# MCU.net
KiCad netlist of a schematic drawn in Altium Designer
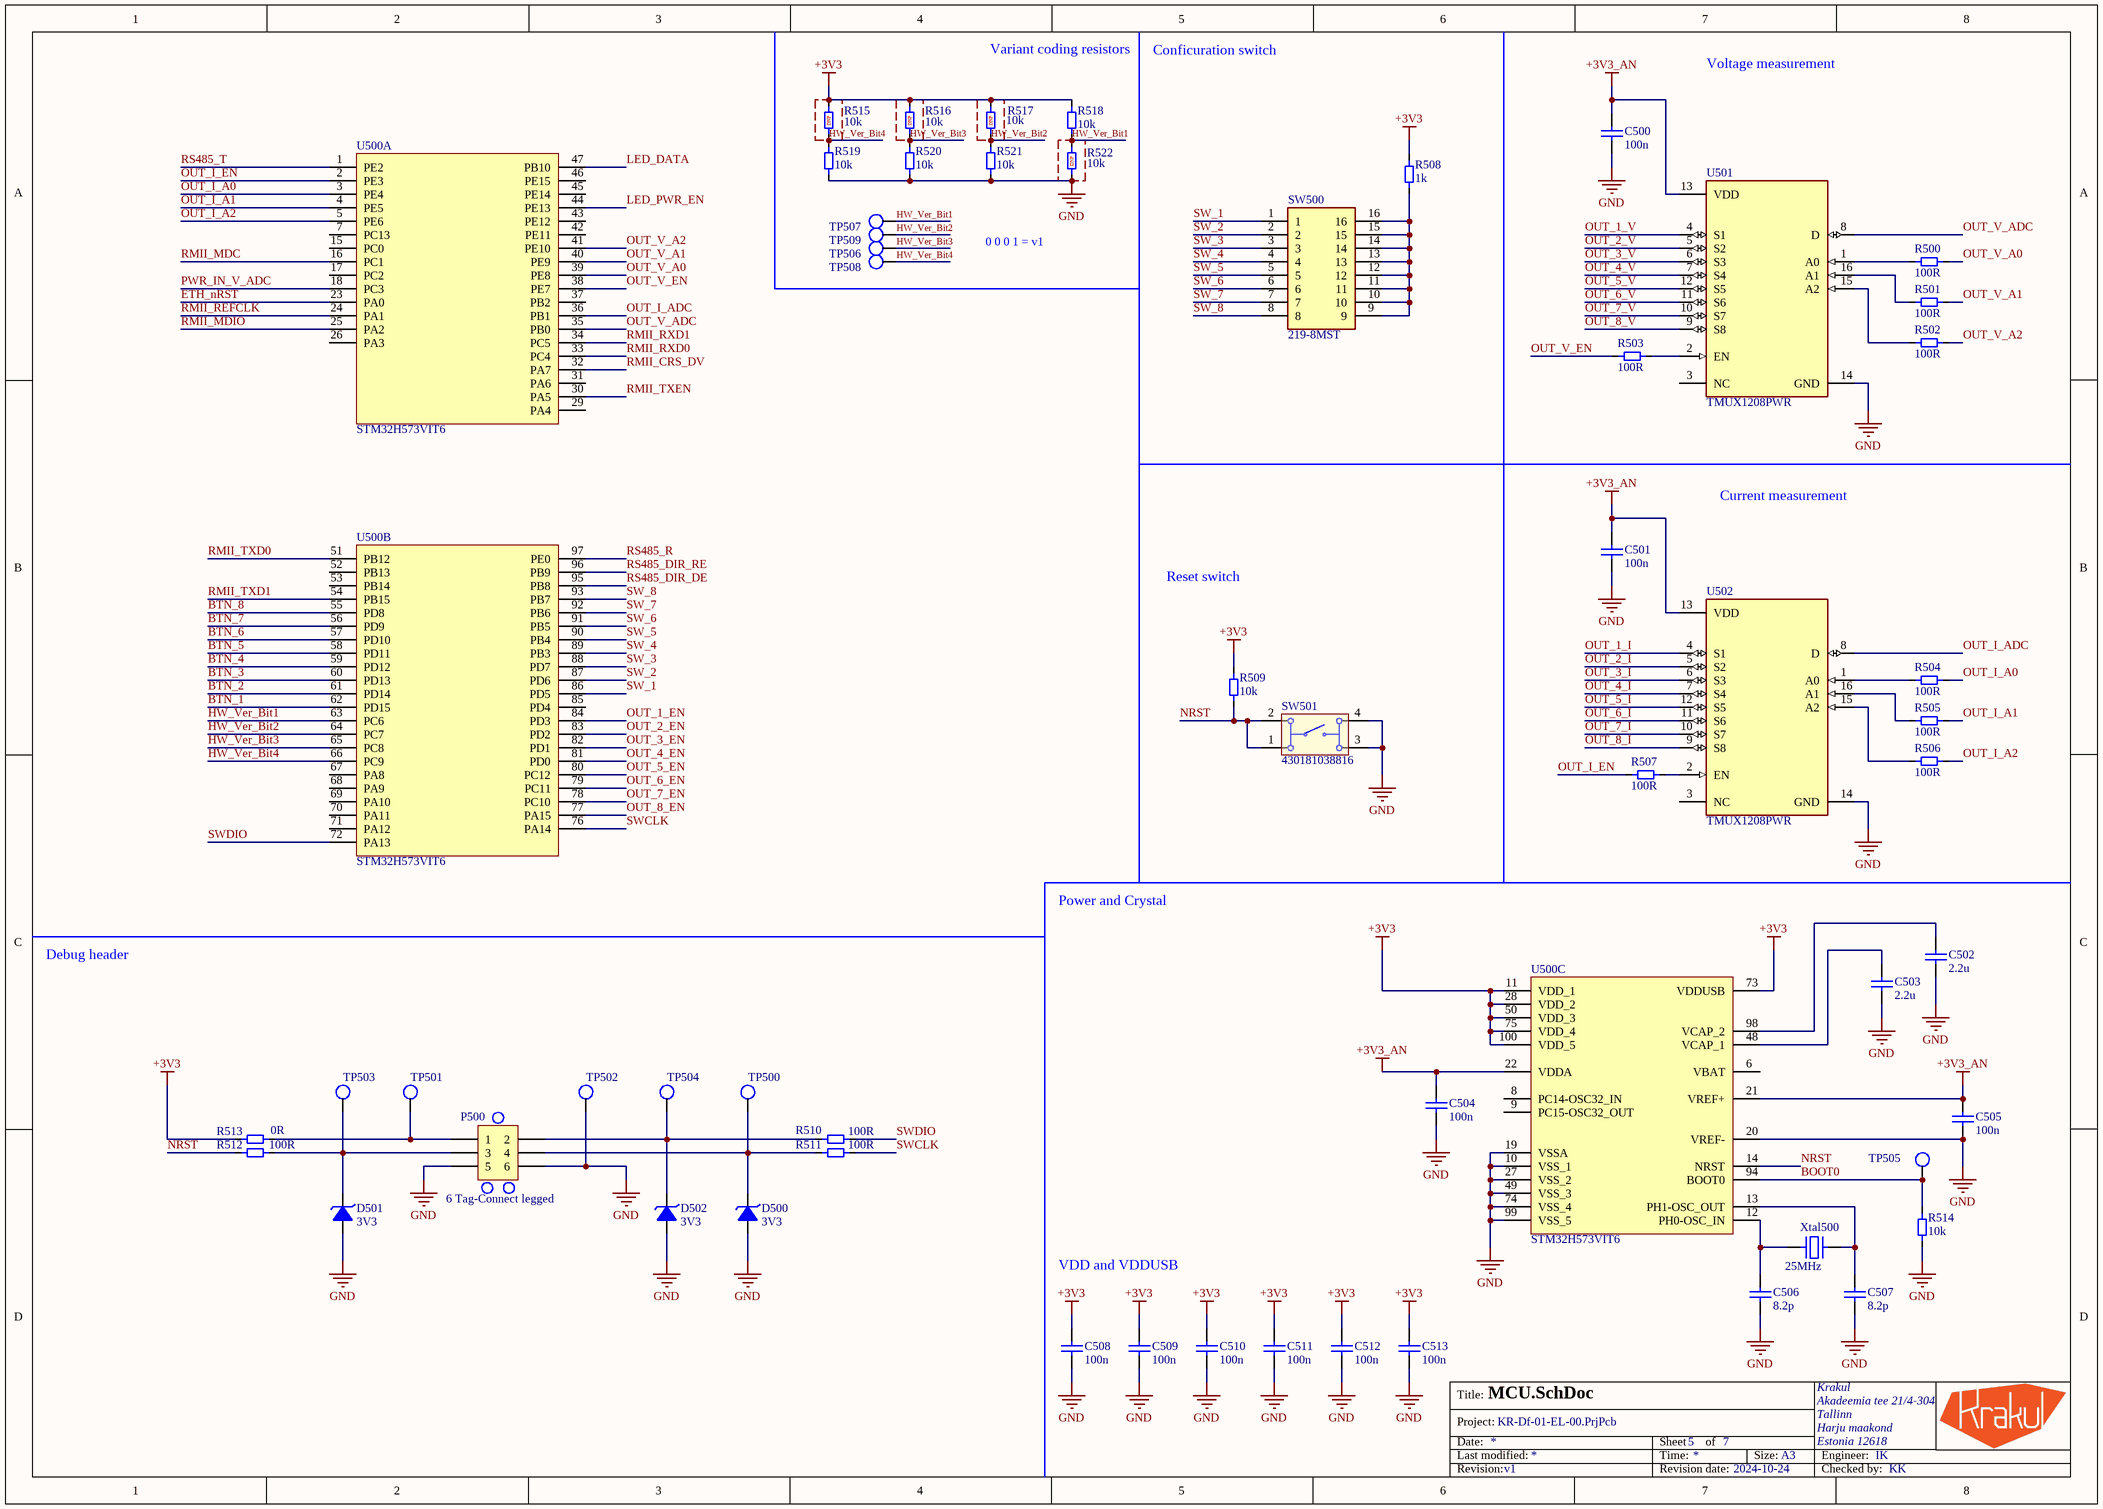
[diagram p0: MCU.SchDoc]

(export (version "E")
  (design (tool "Eeschema 10.0.6"))
  (components
    (comp (ref "C500")
      (value "100n")
      (footprint "MLCC_0402_M")
      (description "MLCC, 0402, 100n, 10%, 10V, X5R")
      (fields (field (name "TOLERANCE") "10%") (field (name "MANUFACTURER") "Any"))
      (libsource (lib "Krakul Vault") (part "CAPACITOR_NONPOL_IEC"))
    )
    (comp (ref "C501")
      (value "100n")
      (footprint "MLCC_0402_M")
      (description "MLCC, 0402, 100n, 10%, 10V, X5R")
      (fields (field (name "TOLERANCE") "10%") (field (name "MANUFACTURER") "Any"))
      (libsource (lib "Krakul Vault") (part "CAPACITOR_NONPOL_IEC"))
    )
    (comp (ref "C502")
      (value "2.2u")
      (footprint "MLCC_0603_M")
      (description "MLCC, 0603, 2.2u, 10%, 16V, X5R")
      (fields (field (name "MANUFACTURER") "Any") (field (name "TOLERANCE") "10%"))
      (libsource (lib "Krakul Vault") (part "CAPACITOR_NONPOL_IEC"))
    )
    (comp (ref "C503")
      (value "2.2u")
      (footprint "MLCC_0603_M")
      (description "MLCC, 0603, 2.2u, 10%, 16V, X5R")
      (fields (field (name "MANUFACTURER") "Any") (field (name "TOLERANCE") "10%"))
      (libsource (lib "Krakul Vault") (part "CAPACITOR_NONPOL_IEC"))
    )
    (comp (ref "C504")
      (value "100n")
      (footprint "MLCC_0402_M")
      (description "MLCC, 0402, 100n, 10%, 10V, X5R")
      (fields (field (name "TOLERANCE") "10%") (field (name "MANUFACTURER") "Any"))
      (libsource (lib "Krakul Vault") (part "CAPACITOR_NONPOL_IEC"))
    )
    (comp (ref "C505")
      (value "100n")
      (footprint "MLCC_0402_M")
      (description "MLCC, 0402, 100n, 10%, 10V, X5R")
      (fields (field (name "TOLERANCE") "10%") (field (name "MANUFACTURER") "Any"))
      (libsource (lib "Krakul Vault") (part "CAPACITOR_NONPOL_IEC"))
    )
    (comp (ref "C506")
      (value "8.2p")
      (footprint "MLCC_0402_M")
      (description "MLCC, 0402, 8.2p, 5%, 50V, C0G/NP0")
      (fields (field (name "MANUFACTURER") "Any") (field (name "VOLTAGE") "50V"))
      (libsource (lib "Krakul Vault") (part "CAPACITOR_NONPOL_IEC"))
    )
    (comp (ref "C507")
      (value "8.2p")
      (footprint "MLCC_0402_M")
      (description "MLCC, 0402, 8.2p, 5%, 50V, C0G/NP0")
      (fields (field (name "MANUFACTURER") "Any") (field (name "VOLTAGE") "50V"))
      (libsource (lib "Krakul Vault") (part "CAPACITOR_NONPOL_IEC"))
    )
    (comp (ref "C508")
      (value "100n")
      (footprint "MLCC_0402_M")
      (description "MLCC, 0402, 100n, 10%, 10V, X5R")
      (fields (field (name "TOLERANCE") "10%") (field (name "MANUFACTURER") "Any"))
      (libsource (lib "Krakul Vault") (part "CAPACITOR_NONPOL_IEC"))
    )
    (comp (ref "C509")
      (value "100n")
      (footprint "MLCC_0402_M")
      (description "MLCC, 0402, 100n, 10%, 10V, X5R")
      (fields (field (name "TOLERANCE") "10%") (field (name "MANUFACTURER") "Any"))
      (libsource (lib "Krakul Vault") (part "CAPACITOR_NONPOL_IEC"))
    )
    (comp (ref "C510")
      (value "100n")
      (footprint "MLCC_0402_M")
      (description "MLCC, 0402, 100n, 10%, 10V, X5R")
      (fields (field (name "TOLERANCE") "10%") (field (name "MANUFACTURER") "Any"))
      (libsource (lib "Krakul Vault") (part "CAPACITOR_NONPOL_IEC"))
    )
    (comp (ref "C511")
      (value "100n")
      (footprint "MLCC_0402_M")
      (description "MLCC, 0402, 100n, 10%, 10V, X5R")
      (fields (field (name "TOLERANCE") "10%") (field (name "MANUFACTURER") "Any"))
      (libsource (lib "Krakul Vault") (part "CAPACITOR_NONPOL_IEC"))
    )
    (comp (ref "C512")
      (value "100n")
      (footprint "MLCC_0402_M")
      (description "MLCC, 0402, 100n, 10%, 10V, X5R")
      (fields (field (name "TOLERANCE") "10%") (field (name "MANUFACTURER") "Any"))
      (libsource (lib "Krakul Vault") (part "CAPACITOR_NONPOL_IEC"))
    )
    (comp (ref "C513")
      (value "100n")
      (footprint "MLCC_0402_M")
      (description "MLCC, 0402, 100n, 10%, 10V, X5R")
      (fields (field (name "TOLERANCE") "10%") (field (name "MANUFACTURER") "Any"))
      (libsource (lib "Krakul Vault") (part "CAPACITOR_NONPOL_IEC"))
    )
    (comp (ref "D500")
      (value "3V3")
      (footprint "SOD-923")
      (description "TVS DIODE 3.3V SOD923")
      (fields (field (name "PART NUMBER") "ESD9X3.3ST5G") (field (name "MANUFACTURER") "ON Semiconductor"))
      (libsource (lib "Krakul Vault") (part "TVS 2 pins"))
    )
    (comp (ref "D501")
      (value "3V3")
      (footprint "SOD-923")
      (description "TVS DIODE 3.3V SOD923")
      (fields (field (name "PART NUMBER") "ESD9X3.3ST5G") (field (name "MANUFACTURER") "ON Semiconductor"))
      (libsource (lib "Krakul Vault") (part "TVS 2 pins"))
    )
    (comp (ref "D502")
      (value "3V3")
      (footprint "SOD-923")
      (description "TVS DIODE 3.3V SOD923")
      (fields (field (name "PART NUMBER") "ESD9X3.3ST5G") (field (name "MANUFACTURER") "ON Semiconductor"))
      (libsource (lib "Krakul Vault") (part "TVS 2 pins"))
    )
    (comp (ref "P500")
      (value "6 Tag-Connect legged")
      (footprint "6P TAG-CONN legged")
      (description "6 Pin Tag-Connect legged")
      (fields
        (field (name "MANUFACTURER") "Tag-Connect")
        (field (name "PART NUMBER") "6pin Tag-Connect legged")
      )
      (libsource (lib "Krakul Vault") (part "6 pos header"))
    )
    (comp (ref "R500")
      (value "100R")
      (footprint "Resistor_0603_M")
      (description "Resistor, 0603, 100R, 1%, 1/10W")
      (fields (field (name "TOLERANCE") "1%") (field (name "POWER") "100mW"))
      (libsource (lib "Krakul Vault") (part "RESISTOR_GENERIC_IEC"))
    )
    (comp (ref "R501")
      (value "100R")
      (footprint "Resistor_0603_M")
      (description "Resistor, 0603, 100R, 1%, 1/10W")
      (fields (field (name "TOLERANCE") "1%") (field (name "POWER") "100mW"))
      (libsource (lib "Krakul Vault") (part "RESISTOR_GENERIC_IEC"))
    )
    (comp (ref "R502")
      (value "100R")
      (footprint "Resistor_0603_M")
      (description "Resistor, 0603, 100R, 1%, 1/10W")
      (fields (field (name "TOLERANCE") "1%") (field (name "POWER") "100mW"))
      (libsource (lib "Krakul Vault") (part "RESISTOR_GENERIC_IEC"))
    )
    (comp (ref "R503")
      (value "100R")
      (footprint "Resistor_0603_M")
      (description "Resistor, 0603, 100R, 1%, 1/10W")
      (fields (field (name "TOLERANCE") "1%") (field (name "POWER") "100mW"))
      (libsource (lib "Krakul Vault") (part "RESISTOR_GENERIC_IEC"))
    )
    (comp (ref "R504")
      (value "100R")
      (footprint "Resistor_0603_M")
      (description "Resistor, 0603, 100R, 1%, 1/10W")
      (fields (field (name "TOLERANCE") "1%") (field (name "POWER") "100mW"))
      (libsource (lib "Krakul Vault") (part "RESISTOR_GENERIC_IEC"))
    )
    (comp (ref "R505")
      (value "100R")
      (footprint "Resistor_0603_M")
      (description "Resistor, 0603, 100R, 1%, 1/10W")
      (fields (field (name "TOLERANCE") "1%") (field (name "POWER") "100mW"))
      (libsource (lib "Krakul Vault") (part "RESISTOR_GENERIC_IEC"))
    )
    (comp (ref "R506")
      (value "100R")
      (footprint "Resistor_0603_M")
      (description "Resistor, 0603, 100R, 1%, 1/10W")
      (fields (field (name "TOLERANCE") "1%") (field (name "POWER") "100mW"))
      (libsource (lib "Krakul Vault") (part "RESISTOR_GENERIC_IEC"))
    )
    (comp (ref "R507")
      (value "100R")
      (footprint "Resistor_0603_M")
      (description "Resistor, 0603, 100R, 1%, 1/10W")
      (fields (field (name "TOLERANCE") "1%") (field (name "POWER") "100mW"))
      (libsource (lib "Krakul Vault") (part "RESISTOR_GENERIC_IEC"))
    )
    (comp (ref "R508")
      (value "1k")
      (footprint "Resistor_0603_M")
      (description "Resistor, 0603, 1k, 0.1%, 1/16W")
      (fields (field (name "MANUFACTURER") "Any"))
      (libsource (lib "Krakul Vault") (part "RESISTOR_GENERIC_IEC"))
    )
    (comp (ref "R509")
      (value "10k")
      (footprint "Resistor_0603_M")
      (description "Resistor, 0603, 10k, 1%, 1/10W")
      (fields (field (name "MANUFACTURER") "Any") (field (name "TOLERANCE") "1%"))
      (libsource (lib "Krakul Vault") (part "RESISTOR_GENERIC_IEC"))
    )
    (comp (ref "R510")
      (value "100R")
      (footprint "Resistor_0603_M")
      (description "Resistor, 0603, 100R, 1%, 1/10W")
      (fields (field (name "TOLERANCE") "1%") (field (name "POWER") "100mW"))
      (libsource (lib "Krakul Vault") (part "RESISTOR_GENERIC_IEC"))
    )
    (comp (ref "R511")
      (value "100R")
      (footprint "Resistor_0603_M")
      (description "Resistor, 0603, 100R, 1%, 1/10W")
      (fields (field (name "TOLERANCE") "1%") (field (name "POWER") "100mW"))
      (libsource (lib "Krakul Vault") (part "RESISTOR_GENERIC_IEC"))
    )
    (comp (ref "R512")
      (value "100R")
      (footprint "Resistor_0603_M")
      (description "Resistor, 0603, 100R, 1%, 1/10W")
      (fields (field (name "TOLERANCE") "1%") (field (name "POWER") "100mW"))
      (libsource (lib "Krakul Vault") (part "RESISTOR_GENERIC_IEC"))
    )
    (comp (ref "R513")
      (value "TLRZ2BTTD")
      (footprint "TLRZ2BTTD-Footprint-1")
      (description "Res Metal Plate 1206 0 Ohm Sulfur Resistant Pad SMD Automotive T/R")
      (fields (field (name "MANUFACTURER") "KOA Speer Electronics") (field (name "VALUE 2") "0R"))
      (libsource (lib "Krakul Vault") (part "RESISTOR_GENERIC_IEC"))
    )
    (comp (ref "R514")
      (value "10k")
      (footprint "Resistor_0603_M")
      (description "Resistor, 0603, 10k, 1%, 1/10W")
      (fields (field (name "MANUFACTURER") "Any") (field (name "TOLERANCE") "1%"))
      (libsource (lib "Krakul Vault") (part "RESISTOR_GENERIC_IEC"))
    )
    (comp (ref "R515")
      (value "10k")
      (footprint "Resistor_0603_M")
      (description "Resistor, 0603, 10k, 1%, 1/10W")
      (fields (field (name "MANUFACTURER") "Any") (field (name "TOLERANCE") "1%"))
      (libsource (lib "Krakul Vault") (part "RESISTOR_GENERIC_IEC"))
    )
    (comp (ref "R516")
      (value "10k")
      (footprint "Resistor_0603_M")
      (description "Resistor, 0603, 10k, 1%, 1/10W")
      (fields (field (name "MANUFACTURER") "Any") (field (name "TOLERANCE") "1%"))
      (libsource (lib "Krakul Vault") (part "RESISTOR_GENERIC_IEC"))
    )
    (comp (ref "R517")
      (value "10k")
      (footprint "Resistor_0603_M")
      (description "Resistor, 0603, 10k, 1%, 1/10W")
      (fields (field (name "MANUFACTURER") "Any") (field (name "TOLERANCE") "1%"))
      (libsource (lib "Krakul Vault") (part "RESISTOR_GENERIC_IEC"))
    )
    (comp (ref "R518")
      (value "10k")
      (footprint "Resistor_0603_M")
      (description "Resistor, 0603, 10k, 1%, 1/10W")
      (fields (field (name "MANUFACTURER") "Any") (field (name "TOLERANCE") "1%"))
      (libsource (lib "Krakul Vault") (part "RESISTOR_GENERIC_IEC"))
    )
    (comp (ref "R519")
      (value "10k")
      (footprint "Resistor_0603_M")
      (description "Resistor, 0603, 10k, 1%, 1/10W")
      (fields (field (name "MANUFACTURER") "Any") (field (name "TOLERANCE") "1%"))
      (libsource (lib "Krakul Vault") (part "RESISTOR_GENERIC_IEC"))
    )
    (comp (ref "R520")
      (value "10k")
      (footprint "Resistor_0603_M")
      (description "Resistor, 0603, 10k, 1%, 1/10W")
      (fields (field (name "MANUFACTURER") "Any") (field (name "TOLERANCE") "1%"))
      (libsource (lib "Krakul Vault") (part "RESISTOR_GENERIC_IEC"))
    )
    (comp (ref "R521")
      (value "10k")
      (footprint "Resistor_0603_M")
      (description "Resistor, 0603, 10k, 1%, 1/10W")
      (fields (field (name "MANUFACTURER") "Any") (field (name "TOLERANCE") "1%"))
      (libsource (lib "Krakul Vault") (part "RESISTOR_GENERIC_IEC"))
    )
    (comp (ref "R522")
      (value "10k")
      (footprint "Resistor_0603_M")
      (description "Resistor, 0603, 10k, 1%, 1/10W")
      (fields (field (name "MANUFACTURER") "Any") (field (name "TOLERANCE") "1%"))
      (libsource (lib "Krakul Vault") (part "RESISTOR_GENERIC_IEC"))
    )
    (comp (ref "SW500")
      (value "219-8MST")
      (footprint "219-8MST-Footprint-1")
      (description "Switch DIP ON OFF SPST 8 Raised Slide 0.1A 20VDC Gull Wing 2000Cycles 2.54mm SMD Tube")
      (fields (field (name "MANUFACTURER") "CTS Electronic Components"))
      (libsource (lib "Krakul Vault") (part "219-8MST-Symbol-1"))
    )
    (comp (ref "SW501")
      (value "430181038816")
      (footprint "430181038816")
      (description "Switch Tactile Spst-no 0.05A 12V")
      (fields (field (name "MANUFACTURER") "Würth Elektronik"))
      (libsource (lib "Krakul Vault") (part "WE-TACT-SW-4_A"))
    )
    (comp (ref "TP500")
      (value "Testpoint 1mm")
      (footprint "Testpoint 1mm")
      (libsource (lib "") (part "Testpoint_1"))
    )
    (comp (ref "TP501")
      (value "Testpoint 1mm")
      (footprint "Testpoint 1mm")
      (libsource (lib "Krakul Vault") (part "Testpoint"))
    )
    (comp (ref "TP502")
      (value "Testpoint 1mm")
      (footprint "Testpoint 1mm")
      (libsource (lib "Krakul Vault") (part "Testpoint"))
    )
    (comp (ref "TP503")
      (value "Testpoint 1mm")
      (footprint "Testpoint 1mm")
      (libsource (lib "Krakul Vault") (part "Testpoint"))
    )
    (comp (ref "TP504")
      (value "Testpoint 1mm")
      (footprint "Testpoint 1mm")
      (libsource (lib "Krakul Vault") (part "Testpoint"))
    )
    (comp (ref "TP505")
      (value "Testpoint 1mm")
      (footprint "Testpoint 1mm")
      (libsource (lib "Krakul Vault") (part "Testpoint"))
    )
    (comp (ref "TP506")
      (value "Testpoint 1mm")
      (footprint "Testpoint 1mm")
      (libsource (lib "Krakul Vault") (part "Testpoint"))
    )
    (comp (ref "TP507")
      (value "Testpoint 1mm")
      (footprint "Testpoint 1mm")
      (libsource (lib "Krakul Vault") (part "Testpoint"))
    )
    (comp (ref "TP508")
      (value "Testpoint 1mm")
      (footprint "Testpoint 1mm")
      (libsource (lib "Krakul Vault") (part "Testpoint"))
    )
    (comp (ref "TP509")
      (value "Testpoint 1mm")
      (footprint "Testpoint 1mm")
      (libsource (lib "Krakul Vault") (part "Testpoint"))
    )
    (comp (ref "U500")
      (value "STM32H573VIT6")
      (footprint "STM32H573VIT6-Footprint-1")
      (fields (field (name "MANUFACTURER") "STMicroelectronics"))
      (libsource (lib "Krakul Vault") (part "STM32H573VIT6-Symbol-1"))
    )
    (comp (ref "U501")
      (value "TMUX1208PWR")
      (footprint "FP-PW0016A-IPC_B")
      (description "5-V, 8: 1, 1-channel general-purpose analog multiplexer with 1.8-V input logic 16-TSSOP -40 to 125")
      (fields (field (name "MANUFACTURER") "TI"))
      (libsource (lib "Krakul Vault") (part "3fc1eebd4caa5623a46538ca285a60d"))
    )
    (comp (ref "U502")
      (value "TMUX1208PWR")
      (footprint "FP-PW0016A-IPC_B")
      (description "5-V, 8: 1, 1-channel general-purpose analog multiplexer with 1.8-V input logic 16-TSSOP -40 to 125")
      (fields (field (name "MANUFACTURER") "TI"))
      (libsource (lib "Krakul Vault") (part "3fc1eebd4caa5623a46538ca285a60d"))
    )
    (comp (ref "Xtal500")
      (value "ECS-250-10-37B-CTN-TR")
      (footprint "4-SMD Crystal 2.00mm x 1.60mm")
      (description "25MHz ±10ppm Crystal 10pF 50 Ohms 4-SMD, No Lead")
      (fields (field (name "FREQUENCY") "25MHz") (field (name "MANUFACTURER") "ECS Inc."))
      (libsource (lib "Krakul Vault") (part "Crystal 4 pins (pins 2, 4 hidden)"))
    )
  )
  (nets
    (net (code "1") (name "+3V3") (class "Default")
      (node (ref "C508") (pin "2") (pinfunction "2_2") (pintype "passive"))
      (node (ref "C509") (pin "2") (pinfunction "2_2") (pintype "passive"))
      (node (ref "C510") (pin "2") (pinfunction "2_2") (pintype "passive"))
      (node (ref "C511") (pin "2") (pinfunction "2_2") (pintype "passive"))
      (node (ref "C512") (pin "2") (pinfunction "2_2") (pintype "passive"))
      (node (ref "C513") (pin "2") (pinfunction "2_2") (pintype "passive"))
      (node (ref "R508") (pin "2") (pinfunction "2_2") (pintype "passive"))
      (node (ref "R509") (pin "2") (pinfunction "2_2") (pintype "passive"))
      (node (ref "R513") (pin "2") (pinfunction "2_2") (pintype "passive"))
      (node (ref "R515") (pin "1") (pinfunction "1_1") (pintype "passive"))
      (node (ref "R516") (pin "2") (pinfunction "2_2") (pintype "passive"))
      (node (ref "R517") (pin "2") (pinfunction "2_2") (pintype "passive"))
      (node (ref "R518") (pin "2") (pinfunction "2_2") (pintype "passive"))
      (node (ref "U500") (pin "100") (pinfunction "VDD_5_100") (pintype "passive"))
      (node (ref "U500") (pin "11") (pinfunction "VDD_1_11") (pintype "passive"))
      (node (ref "U500") (pin "28") (pinfunction "VDD_2_28") (pintype "passive"))
      (node (ref "U500") (pin "50") (pinfunction "VDD_3_50") (pintype "passive"))
      (node (ref "U500") (pin "73") (pinfunction "VDDUSB_73") (pintype "passive"))
      (node (ref "U500") (pin "75") (pinfunction "VDD_4_75") (pintype "passive"))
    )
    (net (code "2") (name "+3V3_AN") (class "Default")
      (node (ref "C500") (pin "2") (pinfunction "2_2") (pintype "passive"))
      (node (ref "C501") (pin "2") (pinfunction "2_2") (pintype "passive"))
      (node (ref "C504") (pin "2") (pinfunction "2_2") (pintype "passive"))
      (node (ref "C505") (pin "2") (pinfunction "2_2") (pintype "passive"))
      (node (ref "U500") (pin "21") (pinfunction "VREF+_21") (pintype "passive"))
      (node (ref "U500") (pin "22") (pinfunction "VDDA_22") (pintype "passive"))
      (node (ref "U501") (pin "13") (pinfunction "VDD_13") (pintype "passive"))
      (node (ref "U502") (pin "13") (pinfunction "VDD_13") (pintype "passive"))
    )
    (net (code "3") (name "/BOOT0") (class "Default")
      (node (ref "R514") (pin "2") (pinfunction "2_2") (pintype "passive"))
      (node (ref "TP505") (pin "1") (pinfunction "1_1") (pintype "passive"))
      (node (ref "U500") (pin "94") (pinfunction "BOOT0_94") (pintype "passive"))
    )
    (net (code "4") (name "/BTN_1") (class "Default")
      (node (ref "U500") (pin "62") (pinfunction "PD15_62") (pintype "passive"))
    )
    (net (code "5") (name "/BTN_2") (class "Default")
      (node (ref "U500") (pin "61") (pinfunction "PD14_61") (pintype "passive"))
    )
    (net (code "6") (name "/BTN_3") (class "Default")
      (node (ref "U500") (pin "60") (pinfunction "PD13_60") (pintype "passive"))
    )
    (net (code "7") (name "/BTN_4") (class "Default")
      (node (ref "U500") (pin "59") (pinfunction "PD12_59") (pintype "passive"))
    )
    (net (code "8") (name "/BTN_5") (class "Default")
      (node (ref "U500") (pin "58") (pinfunction "PD11_58") (pintype "passive"))
    )
    (net (code "9") (name "/BTN_6") (class "Default")
      (node (ref "U500") (pin "57") (pinfunction "PD10_57") (pintype "passive"))
    )
    (net (code "10") (name "/BTN_7") (class "Default")
      (node (ref "U500") (pin "56") (pinfunction "PD9_56") (pintype "passive"))
    )
    (net (code "11") (name "/BTN_8") (class "Default")
      (node (ref "U500") (pin "55") (pinfunction "PD8_55") (pintype "passive"))
    )
    (net (code "12") (name "/ETH_nRST") (class "Default")
      (node (ref "U500") (pin "23") (pinfunction "PA0_23") (pintype "passive"))
    )
    (net (code "13") (name "/HW_Ver_Bit1") (class "Default")
      (node (ref "R518") (pin "1") (pinfunction "1_1") (pintype "passive"))
      (node (ref "R522") (pin "2") (pinfunction "2_2") (pintype "passive"))
      (node (ref "TP507") (pin "1") (pinfunction "1_1") (pintype "passive"))
      (node (ref "U500") (pin "63") (pinfunction "PC6_63") (pintype "passive"))
    )
    (net (code "14") (name "/HW_Ver_Bit2") (class "Default")
      (node (ref "R517") (pin "1") (pinfunction "1_1") (pintype "passive"))
      (node (ref "R521") (pin "2") (pinfunction "2_2") (pintype "passive"))
      (node (ref "TP509") (pin "1") (pinfunction "1_1") (pintype "passive"))
      (node (ref "U500") (pin "64") (pinfunction "PC7_64") (pintype "passive"))
    )
    (net (code "15") (name "/HW_Ver_Bit3") (class "Default")
      (node (ref "R516") (pin "1") (pinfunction "1_1") (pintype "passive"))
      (node (ref "R520") (pin "2") (pinfunction "2_2") (pintype "passive"))
      (node (ref "TP506") (pin "1") (pinfunction "1_1") (pintype "passive"))
      (node (ref "U500") (pin "65") (pinfunction "PC8_65") (pintype "passive"))
    )
    (net (code "16") (name "/HW_Ver_Bit4") (class "Default")
      (node (ref "R515") (pin "2") (pinfunction "2_2") (pintype "passive"))
      (node (ref "R519") (pin "2") (pinfunction "2_2") (pintype "passive"))
      (node (ref "TP508") (pin "1") (pinfunction "1_1") (pintype "passive"))
      (node (ref "U500") (pin "66") (pinfunction "PC9_66") (pintype "passive"))
    )
    (net (code "17") (name "/LED_DATA") (class "Default")
      (node (ref "U500") (pin "47") (pinfunction "PB10_47") (pintype "passive"))
    )
    (net (code "18") (name "/LED_PWR_EN") (class "Default")
      (node (ref "U500") (pin "44") (pinfunction "PE13_44") (pintype "passive"))
    )
    (net (code "19") (name "/NRST") (class "Default")
      (node (ref "R509") (pin "1") (pinfunction "1_1") (pintype "passive"))
      (node (ref "R512") (pin "2") (pinfunction "2_2") (pintype "passive"))
      (node (ref "SW501") (pin "1") (pinfunction "1_1") (pintype "passive"))
      (node (ref "SW501") (pin "2") (pinfunction "2_2") (pintype "passive"))
      (node (ref "U500") (pin "14") (pinfunction "NRST_14") (pintype "passive"))
    )
    (net (code "20") (name "/OUT_1_EN") (class "Default")
      (node (ref "U500") (pin "84") (pinfunction "PD3_84") (pintype "passive"))
    )
    (net (code "21") (name "/OUT_1_I") (class "Default")
      (node (ref "U502") (pin "4") (pinfunction "S1_4") (pintype "bidirectional"))
    )
    (net (code "22") (name "/OUT_1_V") (class "Default")
      (node (ref "U501") (pin "4") (pinfunction "S1_4") (pintype "bidirectional"))
    )
    (net (code "23") (name "/OUT_2_EN") (class "Default")
      (node (ref "U500") (pin "83") (pinfunction "PD2_83") (pintype "passive"))
    )
    (net (code "24") (name "/OUT_2_I") (class "Default")
      (node (ref "U502") (pin "5") (pinfunction "S2_5") (pintype "bidirectional"))
    )
    (net (code "25") (name "/OUT_2_V") (class "Default")
      (node (ref "U501") (pin "5") (pinfunction "S2_5") (pintype "bidirectional"))
    )
    (net (code "26") (name "/OUT_3_EN") (class "Default")
      (node (ref "U500") (pin "82") (pinfunction "PD1_82") (pintype "passive"))
    )
    (net (code "27") (name "/OUT_3_I") (class "Default")
      (node (ref "U502") (pin "6") (pinfunction "S3_6") (pintype "bidirectional"))
    )
    (net (code "28") (name "/OUT_3_V") (class "Default")
      (node (ref "U501") (pin "6") (pinfunction "S3_6") (pintype "bidirectional"))
    )
    (net (code "29") (name "/OUT_4_EN") (class "Default")
      (node (ref "U500") (pin "81") (pinfunction "PD0_81") (pintype "passive"))
    )
    (net (code "30") (name "/OUT_4_I") (class "Default")
      (node (ref "U502") (pin "7") (pinfunction "S4_7") (pintype "bidirectional"))
    )
    (net (code "31") (name "/OUT_4_V") (class "Default")
      (node (ref "U501") (pin "7") (pinfunction "S4_7") (pintype "bidirectional"))
    )
    (net (code "32") (name "/OUT_5_EN") (class "Default")
      (node (ref "U500") (pin "80") (pinfunction "PC12_80") (pintype "passive"))
    )
    (net (code "33") (name "/OUT_5_I") (class "Default")
      (node (ref "U502") (pin "12") (pinfunction "S5_12") (pintype "bidirectional"))
    )
    (net (code "34") (name "/OUT_5_V") (class "Default")
      (node (ref "U501") (pin "12") (pinfunction "S5_12") (pintype "bidirectional"))
    )
    (net (code "35") (name "/OUT_6_EN") (class "Default")
      (node (ref "U500") (pin "79") (pinfunction "PC11_79") (pintype "passive"))
    )
    (net (code "36") (name "/OUT_6_I") (class "Default")
      (node (ref "U502") (pin "11") (pinfunction "S6_11") (pintype "bidirectional"))
    )
    (net (code "37") (name "/OUT_6_V") (class "Default")
      (node (ref "U501") (pin "11") (pinfunction "S6_11") (pintype "bidirectional"))
    )
    (net (code "38") (name "/OUT_7_EN") (class "Default")
      (node (ref "U500") (pin "78") (pinfunction "PC10_78") (pintype "passive"))
    )
    (net (code "39") (name "/OUT_7_I") (class "Default")
      (node (ref "U502") (pin "10") (pinfunction "S7_10") (pintype "bidirectional"))
    )
    (net (code "40") (name "/OUT_7_V") (class "Default")
      (node (ref "U501") (pin "10") (pinfunction "S7_10") (pintype "bidirectional"))
    )
    (net (code "41") (name "/OUT_8_EN") (class "Default")
      (node (ref "U500") (pin "77") (pinfunction "PA15_77") (pintype "passive"))
    )
    (net (code "42") (name "/OUT_8_I") (class "Default")
      (node (ref "U502") (pin "9") (pinfunction "S8_9") (pintype "bidirectional"))
    )
    (net (code "43") (name "/OUT_8_V") (class "Default")
      (node (ref "U501") (pin "9") (pinfunction "S8_9") (pintype "bidirectional"))
    )
    (net (code "44") (name "/OUT_I_A0") (class "Default")
      (node (ref "R504") (pin "2") (pinfunction "2_2") (pintype "passive"))
      (node (ref "U500") (pin "3") (pinfunction "PE4_3") (pintype "passive"))
    )
    (net (code "45") (name "/OUT_I_A1") (class "Default")
      (node (ref "R505") (pin "2") (pinfunction "2_2") (pintype "passive"))
      (node (ref "U500") (pin "4") (pinfunction "PE5_4") (pintype "passive"))
    )
    (net (code "46") (name "/OUT_I_A2") (class "Default")
      (node (ref "R506") (pin "2") (pinfunction "2_2") (pintype "passive"))
      (node (ref "U500") (pin "5") (pinfunction "PE6_5") (pintype "passive"))
    )
    (net (code "47") (name "/OUT_I_ADC") (class "Default")
      (node (ref "U500") (pin "36") (pinfunction "PB1_36") (pintype "passive"))
      (node (ref "U502") (pin "8") (pinfunction "D_8") (pintype "bidirectional"))
    )
    (net (code "48") (name "/OUT_I_EN") (class "Default")
      (node (ref "R507") (pin "1") (pinfunction "1_1") (pintype "passive"))
      (node (ref "U500") (pin "2") (pinfunction "PE3_2") (pintype "passive"))
    )
    (net (code "49") (name "/OUT_V_A0") (class "Default")
      (node (ref "R500") (pin "2") (pinfunction "2_2") (pintype "passive"))
      (node (ref "U500") (pin "39") (pinfunction "PE8_39") (pintype "passive"))
    )
    (net (code "50") (name "/OUT_V_A1") (class "Default")
      (node (ref "R501") (pin "2") (pinfunction "2_2") (pintype "passive"))
      (node (ref "U500") (pin "40") (pinfunction "PE9_40") (pintype "passive"))
    )
    (net (code "51") (name "/OUT_V_A2") (class "Default")
      (node (ref "R502") (pin "2") (pinfunction "2_2") (pintype "passive"))
      (node (ref "U500") (pin "41") (pinfunction "PE10_41") (pintype "passive"))
    )
    (net (code "52") (name "/OUT_V_ADC") (class "Default")
      (node (ref "U500") (pin "35") (pinfunction "PB0_35") (pintype "passive"))
      (node (ref "U501") (pin "8") (pinfunction "D_8") (pintype "bidirectional"))
    )
    (net (code "53") (name "/OUT_V_EN") (class "Default")
      (node (ref "R503") (pin "1") (pinfunction "1_1") (pintype "passive"))
      (node (ref "U500") (pin "38") (pinfunction "PE7_38") (pintype "passive"))
    )
    (net (code "54") (name "/PWR_IN_V_ADC") (class "Default")
      (node (ref "U500") (pin "18") (pinfunction "PC3_18") (pintype "passive"))
    )
    (net (code "55") (name "/RMII_CRS_DV") (class "Default")
      (node (ref "U500") (pin "32") (pinfunction "PA7_32") (pintype "passive"))
    )
    (net (code "56") (name "/RMII_MDC") (class "Default")
      (node (ref "U500") (pin "16") (pinfunction "PC1_16") (pintype "passive"))
    )
    (net (code "57") (name "/RMII_MDIO") (class "Default")
      (node (ref "U500") (pin "25") (pinfunction "PA2_25") (pintype "passive"))
    )
    (net (code "58") (name "/RMII_REFCLK") (class "Default")
      (node (ref "U500") (pin "24") (pinfunction "PA1_24") (pintype "passive"))
    )
    (net (code "59") (name "/RMII_RXD0") (class "Default")
      (node (ref "U500") (pin "33") (pinfunction "PC4_33") (pintype "passive"))
    )
    (net (code "60") (name "/RMII_RXD1") (class "Default")
      (node (ref "U500") (pin "34") (pinfunction "PC5_34") (pintype "passive"))
    )
    (net (code "61") (name "/RMII_TXD0") (class "Default")
      (node (ref "U500") (pin "51") (pinfunction "PB12_51") (pintype "passive"))
    )
    (net (code "62") (name "/RMII_TXD1") (class "Default")
      (node (ref "U500") (pin "54") (pinfunction "PB15_54") (pintype "passive"))
    )
    (net (code "63") (name "/RMII_TXEN") (class "Default")
      (node (ref "U500") (pin "30") (pinfunction "PA5_30") (pintype "passive"))
    )
    (net (code "64") (name "/RS485_DIR_DE") (class "Default")
      (node (ref "U500") (pin "95") (pinfunction "PB8_95") (pintype "passive"))
    )
    (net (code "65") (name "/RS485_DIR_RE") (class "Default")
      (node (ref "U500") (pin "96") (pinfunction "PB9_96") (pintype "passive"))
    )
    (net (code "66") (name "/RS485_R") (class "Default")
      (node (ref "U500") (pin "97") (pinfunction "PE0_97") (pintype "passive"))
    )
    (net (code "67") (name "/RS485_T") (class "Default")
      (node (ref "U500") (pin "1") (pinfunction "PE2_1") (pintype "passive"))
    )
    (net (code "68") (name "/SWCLK") (class "Default")
      (node (ref "R511") (pin "1") (pinfunction "1_1") (pintype "passive"))
      (node (ref "U500") (pin "76") (pinfunction "PA14_76") (pintype "passive"))
    )
    (net (code "69") (name "/SWDIO") (class "Default")
      (node (ref "R510") (pin "2") (pinfunction "2_2") (pintype "passive"))
      (node (ref "U500") (pin "72") (pinfunction "PA13_72") (pintype "passive"))
    )
    (net (code "70") (name "/SW_1") (class "Default")
      (node (ref "SW500") (pin "1") (pinfunction "1_1") (pintype "passive"))
      (node (ref "U500") (pin "86") (pinfunction "PD5_86") (pintype "passive"))
    )
    (net (code "71") (name "/SW_2") (class "Default")
      (node (ref "SW500") (pin "2") (pinfunction "2_2") (pintype "passive"))
      (node (ref "U500") (pin "87") (pinfunction "PD6_87") (pintype "passive"))
    )
    (net (code "72") (name "/SW_3") (class "Default")
      (node (ref "SW500") (pin "3") (pinfunction "3_3") (pintype "passive"))
      (node (ref "U500") (pin "88") (pinfunction "PD7_88") (pintype "passive"))
    )
    (net (code "73") (name "/SW_4") (class "Default")
      (node (ref "SW500") (pin "4") (pinfunction "4_4") (pintype "passive"))
      (node (ref "U500") (pin "89") (pinfunction "PB3_89") (pintype "passive"))
    )
    (net (code "74") (name "/SW_5") (class "Default")
      (node (ref "SW500") (pin "5") (pinfunction "5_5") (pintype "passive"))
      (node (ref "U500") (pin "90") (pinfunction "PB4_90") (pintype "passive"))
    )
    (net (code "75") (name "/SW_6") (class "Default")
      (node (ref "SW500") (pin "6") (pinfunction "6_6") (pintype "passive"))
      (node (ref "U500") (pin "91") (pinfunction "PB5_91") (pintype "passive"))
    )
    (net (code "76") (name "/SW_7") (class "Default")
      (node (ref "SW500") (pin "7") (pinfunction "7_7") (pintype "passive"))
      (node (ref "U500") (pin "92") (pinfunction "PB6_92") (pintype "passive"))
    )
    (net (code "77") (name "/SW_8") (class "Default")
      (node (ref "SW500") (pin "8") (pinfunction "8_8") (pintype "passive"))
      (node (ref "U500") (pin "93") (pinfunction "PB7_93") (pintype "passive"))
    )
    (net (code "78") (name "GND") (class "Default")
      (node (ref "C500") (pin "1") (pinfunction "1_1") (pintype "passive"))
      (node (ref "C501") (pin "1") (pinfunction "1_1") (pintype "passive"))
      (node (ref "C502") (pin "1") (pinfunction "1_1") (pintype "passive"))
      (node (ref "C503") (pin "1") (pinfunction "1_1") (pintype "passive"))
      (node (ref "C504") (pin "1") (pinfunction "1_1") (pintype "passive"))
      (node (ref "C505") (pin "1") (pinfunction "1_1") (pintype "passive"))
      (node (ref "C506") (pin "1") (pinfunction "1_1") (pintype "passive"))
      (node (ref "C507") (pin "1") (pinfunction "1_1") (pintype "passive"))
      (node (ref "C508") (pin "1") (pinfunction "1_1") (pintype "passive"))
      (node (ref "C509") (pin "1") (pinfunction "1_1") (pintype "passive"))
      (node (ref "C510") (pin "1") (pinfunction "1_1") (pintype "passive"))
      (node (ref "C511") (pin "1") (pinfunction "1_1") (pintype "passive"))
      (node (ref "C512") (pin "1") (pinfunction "1_1") (pintype "passive"))
      (node (ref "C513") (pin "1") (pinfunction "1_1") (pintype "passive"))
      (node (ref "D500") (pin "2") (pinfunction "A_2") (pintype "passive"))
      (node (ref "D501") (pin "2") (pinfunction "A_2") (pintype "passive"))
      (node (ref "D502") (pin "2") (pinfunction "A_2") (pintype "passive"))
      (node (ref "P500") (pin "5") (pinfunction "5_5") (pintype "passive"))
      (node (ref "P500") (pin "6") (pinfunction "6_6") (pintype "passive"))
      (node (ref "R514") (pin "1") (pinfunction "1_1") (pintype "passive"))
      (node (ref "R519") (pin "1") (pinfunction "1_1") (pintype "passive"))
      (node (ref "R520") (pin "1") (pinfunction "1_1") (pintype "passive"))
      (node (ref "R521") (pin "1") (pinfunction "1_1") (pintype "passive"))
      (node (ref "R522") (pin "1") (pinfunction "1_1") (pintype "passive"))
      (node (ref "SW501") (pin "3") (pinfunction "3_3") (pintype "passive"))
      (node (ref "SW501") (pin "4") (pinfunction "4_4") (pintype "passive"))
      (node (ref "TP502") (pin "1") (pinfunction "1_1") (pintype "passive"))
      (node (ref "U500") (pin "10") (pinfunction "VSS_1_10") (pintype "passive"))
      (node (ref "U500") (pin "19") (pinfunction "VSSA_19") (pintype "passive"))
      (node (ref "U500") (pin "20") (pinfunction "VREF-_20") (pintype "passive"))
      (node (ref "U500") (pin "27") (pinfunction "VSS_2_27") (pintype "passive"))
      (node (ref "U500") (pin "49") (pinfunction "VSS_3_49") (pintype "passive"))
      (node (ref "U500") (pin "74") (pinfunction "VSS_4_74") (pintype "passive"))
      (node (ref "U500") (pin "99") (pinfunction "VSS_5_99") (pintype "passive"))
      (node (ref "U501") (pin "14") (pinfunction "GND_14") (pintype "power_in"))
      (node (ref "U502") (pin "14") (pinfunction "GND_14") (pintype "power_in"))
      (node (ref "Xtal500") (pin "2") (pinfunction "GND_2") (pintype "power_in"))
      (node (ref "Xtal500") (pin "4") (pinfunction "GND_4") (pintype "power_in"))
    )
    (net (code "79") (name "Net-(D500-C)") (class "Default")
      (node (ref "D500") (pin "1") (pinfunction "C_1") (pintype "passive"))
      (node (ref "P500") (pin "4") (pinfunction "4_4") (pintype "passive"))
      (node (ref "R511") (pin "2") (pinfunction "2_2") (pintype "passive"))
      (node (ref "TP500") (pin "1") (pinfunction "1_1") (pintype "passive"))
    )
    (net (code "80") (name "Net-(D501-C)") (class "Default")
      (node (ref "D501") (pin "1") (pinfunction "C_1") (pintype "passive"))
      (node (ref "P500") (pin "3") (pinfunction "3_3") (pintype "passive"))
      (node (ref "R512") (pin "1") (pinfunction "1_1") (pintype "passive"))
      (node (ref "TP503") (pin "1") (pinfunction "1_1") (pintype "passive"))
    )
    (net (code "81") (name "Net-(D502-C)") (class "Default")
      (node (ref "D502") (pin "1") (pinfunction "C_1") (pintype "passive"))
      (node (ref "P500") (pin "2") (pinfunction "2_2") (pintype "passive"))
      (node (ref "R510") (pin "1") (pinfunction "1_1") (pintype "passive"))
      (node (ref "TP504") (pin "1") (pinfunction "1_1") (pintype "passive"))
    )
    (net (code "82") (name "Net-(P500-Pad1)") (class "Default")
      (node (ref "P500") (pin "1") (pinfunction "1_1") (pintype "passive"))
      (node (ref "R513") (pin "1") (pinfunction "1_1") (pintype "passive"))
      (node (ref "TP501") (pin "1") (pinfunction "1_1") (pintype "passive"))
    )
    (net (code "83") (name "Net-(R508-Pad1)") (class "Default")
      (node (ref "R508") (pin "1") (pinfunction "1_1") (pintype "passive"))
      (node (ref "SW500") (pin "10") (pinfunction "10_10") (pintype "passive"))
      (node (ref "SW500") (pin "11") (pinfunction "11_11") (pintype "passive"))
      (node (ref "SW500") (pin "12") (pinfunction "12_12") (pintype "passive"))
      (node (ref "SW500") (pin "13") (pinfunction "13_13") (pintype "passive"))
      (node (ref "SW500") (pin "14") (pinfunction "14_14") (pintype "passive"))
      (node (ref "SW500") (pin "15") (pinfunction "15_15") (pintype "passive"))
      (node (ref "SW500") (pin "16") (pinfunction "16_16") (pintype "passive"))
      (node (ref "SW500") (pin "9") (pinfunction "9_9") (pintype "passive"))
    )
    (net (code "84") (name "Net-(U500C-PH0-OSC_IN)") (class "Default")
      (node (ref "C506") (pin "2") (pinfunction "2_2") (pintype "passive"))
      (node (ref "U500") (pin "12") (pinfunction "PH0-OSC_IN_12") (pintype "passive"))
      (node (ref "Xtal500") (pin "1") (pinfunction "1_1") (pintype "passive"))
    )
    (net (code "85") (name "Net-(U500C-PH1-OSC_OUT)") (class "Default")
      (node (ref "C507") (pin "2") (pinfunction "2_2") (pintype "passive"))
      (node (ref "U500") (pin "13") (pinfunction "PH1-OSC_OUT_13") (pintype "passive"))
      (node (ref "Xtal500") (pin "3") (pinfunction "3_3") (pintype "passive"))
    )
    (net (code "86") (name "Net-(U500C-VCAP_1)") (class "Default")
      (node (ref "C503") (pin "2") (pinfunction "2_2") (pintype "passive"))
      (node (ref "U500") (pin "48") (pinfunction "VCAP_1_48") (pintype "passive"))
    )
    (net (code "87") (name "Net-(U500C-VCAP_2)") (class "Default")
      (node (ref "C502") (pin "2") (pinfunction "2_2") (pintype "passive"))
      (node (ref "U500") (pin "98") (pinfunction "VCAP_2_98") (pintype "passive"))
    )
    (net (code "88") (name "Net-(U501-A0)") (class "Default")
      (node (ref "R500") (pin "1") (pinfunction "1_1") (pintype "passive"))
      (node (ref "U501") (pin "1") (pinfunction "A0_1") (pintype "input"))
    )
    (net (code "89") (name "Net-(U501-A1)") (class "Default")
      (node (ref "R501") (pin "1") (pinfunction "1_1") (pintype "passive"))
      (node (ref "U501") (pin "16") (pinfunction "A1_16") (pintype "input"))
    )
    (net (code "90") (name "Net-(U501-A2)") (class "Default")
      (node (ref "R502") (pin "1") (pinfunction "1_1") (pintype "passive"))
      (node (ref "U501") (pin "15") (pinfunction "A2_15") (pintype "input"))
    )
    (net (code "91") (name "Net-(U501-EN)") (class "Default")
      (node (ref "R503") (pin "2") (pinfunction "2_2") (pintype "passive"))
      (node (ref "U501") (pin "2") (pinfunction "EN_2") (pintype "input"))
    )
    (net (code "92") (name "Net-(U502-A0)") (class "Default")
      (node (ref "R504") (pin "1") (pinfunction "1_1") (pintype "passive"))
      (node (ref "U502") (pin "1") (pinfunction "A0_1") (pintype "input"))
    )
    (net (code "93") (name "Net-(U502-A1)") (class "Default")
      (node (ref "R505") (pin "1") (pinfunction "1_1") (pintype "passive"))
      (node (ref "U502") (pin "16") (pinfunction "A1_16") (pintype "input"))
    )
    (net (code "94") (name "Net-(U502-A2)") (class "Default")
      (node (ref "R506") (pin "1") (pinfunction "1_1") (pintype "passive"))
      (node (ref "U502") (pin "15") (pinfunction "A2_15") (pintype "input"))
    )
    (net (code "95") (name "Net-(U502-EN)") (class "Default")
      (node (ref "R507") (pin "2") (pinfunction "2_2") (pintype "passive"))
      (node (ref "U502") (pin "2") (pinfunction "EN_2") (pintype "input"))
    )
    (net (code "96") (name "unconnected-(U500A-PA3-Pad26)") (class "Default")
      (node (ref "U500") (pin "26") (pinfunction "PA3_26") (pintype "passive"))
    )
    (net (code "97") (name "unconnected-(U500A-PA4-Pad29)") (class "Default")
      (node (ref "U500") (pin "29") (pinfunction "PA4_29") (pintype "passive"))
    )
    (net (code "98") (name "unconnected-(U500A-PA6-Pad31)") (class "Default")
      (node (ref "U500") (pin "31") (pinfunction "PA6_31") (pintype "passive"))
    )
    (net (code "99") (name "unconnected-(U500A-PB2-Pad37)") (class "Default")
      (node (ref "U500") (pin "37") (pinfunction "PB2_37") (pintype "passive"))
    )
    (net (code "100") (name "unconnected-(U500A-PC0-Pad15)") (class "Default")
      (node (ref "U500") (pin "15") (pinfunction "PC0_15") (pintype "passive"))
    )
    (net (code "101") (name "unconnected-(U500A-PC2-Pad17)") (class "Default")
      (node (ref "U500") (pin "17") (pinfunction "PC2_17") (pintype "passive"))
    )
    (net (code "102") (name "unconnected-(U500A-PC13-Pad7)") (class "Default")
      (node (ref "U500") (pin "7") (pinfunction "PC13_7") (pintype "passive"))
    )
    (net (code "103") (name "unconnected-(U500A-PE11-Pad42)") (class "Default")
      (node (ref "U500") (pin "42") (pinfunction "PE11_42") (pintype "passive"))
    )
    (net (code "104") (name "unconnected-(U500A-PE12-Pad43)") (class "Default")
      (node (ref "U500") (pin "43") (pinfunction "PE12_43") (pintype "passive"))
    )
    (net (code "105") (name "unconnected-(U500A-PE14-Pad45)") (class "Default")
      (node (ref "U500") (pin "45") (pinfunction "PE14_45") (pintype "passive"))
    )
    (net (code "106") (name "unconnected-(U500A-PE15-Pad46)") (class "Default")
      (node (ref "U500") (pin "46") (pinfunction "PE15_46") (pintype "passive"))
    )
    (net (code "107") (name "unconnected-(U500B-PA8-Pad67)") (class "Default")
      (node (ref "U500") (pin "67") (pinfunction "PA8_67") (pintype "passive"))
    )
    (net (code "108") (name "unconnected-(U500B-PA9-Pad68)") (class "Default")
      (node (ref "U500") (pin "68") (pinfunction "PA9_68") (pintype "passive"))
    )
    (net (code "109") (name "unconnected-(U500B-PA10-Pad69)") (class "Default")
      (node (ref "U500") (pin "69") (pinfunction "PA10_69") (pintype "passive"))
    )
    (net (code "110") (name "unconnected-(U500B-PA11-Pad70)") (class "Default")
      (node (ref "U500") (pin "70") (pinfunction "PA11_70") (pintype "passive"))
    )
    (net (code "111") (name "unconnected-(U500B-PA12-Pad71)") (class "Default")
      (node (ref "U500") (pin "71") (pinfunction "PA12_71") (pintype "passive"))
    )
    (net (code "112") (name "unconnected-(U500B-PB13-Pad52)") (class "Default")
      (node (ref "U500") (pin "52") (pinfunction "PB13_52") (pintype "passive"))
    )
    (net (code "113") (name "unconnected-(U500B-PB14-Pad53)") (class "Default")
      (node (ref "U500") (pin "53") (pinfunction "PB14_53") (pintype "passive"))
    )
    (net (code "114") (name "unconnected-(U500B-PD4-Pad85)") (class "Default")
      (node (ref "U500") (pin "85") (pinfunction "PD4_85") (pintype "passive"))
    )
    (net (code "115") (name "unconnected-(U500C-PC14-OSC32_IN-Pad8)") (class "Default")
      (node (ref "U500") (pin "8") (pinfunction "PC14-OSC32_IN_8") (pintype "passive"))
    )
    (net (code "116") (name "unconnected-(U500C-PC15-OSC32_OUT-Pad9)") (class "Default")
      (node (ref "U500") (pin "9") (pinfunction "PC15-OSC32_OUT_9") (pintype "passive"))
    )
    (net (code "117") (name "unconnected-(U500C-VBAT-Pad6)") (class "Default")
      (node (ref "U500") (pin "6") (pinfunction "VBAT_6") (pintype "passive"))
    )
    (net (code "118") (name "unconnected-(U501-NC-Pad3)") (class "Default")
      (node (ref "U501") (pin "3") (pinfunction "NC_3") (pintype "passive"))
    )
    (net (code "119") (name "unconnected-(U502-NC-Pad3)") (class "Default")
      (node (ref "U502") (pin "3") (pinfunction "NC_3") (pintype "passive"))
    )
  )
)
